# Schematic_Buttons_Luximetro.net
KiCad netlist of a schematic drawn in Altium Designer
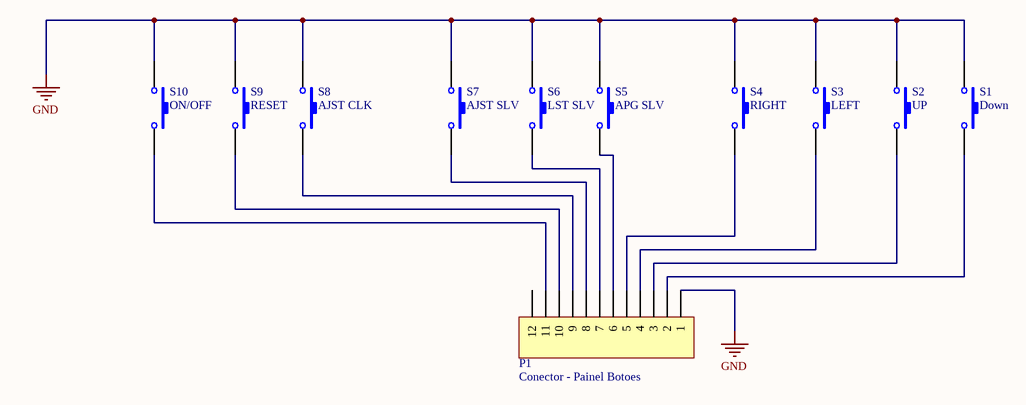
[diagram p0: Schematic_Buttons_Luximetro.SchDoc]

(export (version "E")
  (design (tool "Eeschema 10.0.6"))
  (components
    (comp (ref "P1")
      (value "Conector - Painel Botoes")
      (footprint "HDR1X12")
      (description "Header, 12-Pin")
      (fields (field (name "PUBLISHER") "Altium Limited"))
      (libsource (lib "Miscellaneous Connectors") (part "Header 12"))
    )
    (comp (ref "S1")
      (value "Down")
      (footprint "SPST-2")
      (description "Switch")
      (fields (field (name "PUBLISHER") "Altium Limited"))
      (libsource (lib "Miscellaneous Devices") (part "SW-PB"))
    )
    (comp (ref "S2")
      (value "UP")
      (footprint "SPST-2")
      (description "Switch")
      (fields (field (name "PUBLISHER") "Altium Limited"))
      (libsource (lib "Miscellaneous Devices") (part "SW-PB"))
    )
    (comp (ref "S3")
      (value "LEFT")
      (footprint "SPST-2")
      (description "Switch")
      (fields (field (name "PUBLISHER") "Altium Limited"))
      (libsource (lib "Miscellaneous Devices") (part "SW-PB"))
    )
    (comp (ref "S4")
      (value "RIGHT")
      (footprint "SPST-2")
      (description "Switch")
      (fields (field (name "PUBLISHER") "Altium Limited"))
      (libsource (lib "Miscellaneous Devices") (part "SW-PB"))
    )
    (comp (ref "S5")
      (value "APG SLV")
      (footprint "SPST-2")
      (description "Switch")
      (fields (field (name "PUBLISHER") "Altium Limited"))
      (libsource (lib "Miscellaneous Devices") (part "SW-PB"))
    )
    (comp (ref "S6")
      (value "LST SLV")
      (footprint "SPST-2")
      (description "Switch")
      (fields (field (name "PUBLISHER") "Altium Limited"))
      (libsource (lib "Miscellaneous Devices") (part "SW-PB"))
    )
    (comp (ref "S7")
      (value "AJST SLV")
      (footprint "SPST-2")
      (description "Switch")
      (fields (field (name "PUBLISHER") "Altium Limited"))
      (libsource (lib "Miscellaneous Devices") (part "SW-PB"))
    )
    (comp (ref "S8")
      (value "AJST CLK")
      (footprint "SPST-2")
      (description "Switch")
      (fields (field (name "PUBLISHER") "Altium Limited"))
      (libsource (lib "Miscellaneous Devices") (part "SW-PB"))
    )
    (comp (ref "S9")
      (value "RESET")
      (footprint "SPST-2")
      (description "Switch")
      (fields (field (name "PUBLISHER") "Altium Limited"))
      (libsource (lib "Miscellaneous Devices") (part "SW-PB"))
    )
    (comp (ref "S10")
      (value "ON/OFF")
      (footprint "SPST-2")
      (description "Switch")
      (fields (field (name "PUBLISHER") "Altium Limited"))
      (libsource (lib "Miscellaneous Devices") (part "SW-PB"))
    )
  )
  (nets
    (net (code "1") (name "GND") (class "Default")
      (node (ref "P1") (pin "1") (pinfunction "1_1") (pintype "passive"))
      (node (ref "S1") (pin "1") (pinfunction "1_1") (pintype "passive"))
      (node (ref "S10") (pin "1") (pinfunction "1_1") (pintype "passive"))
      (node (ref "S2") (pin "1") (pinfunction "1_1") (pintype "passive"))
      (node (ref "S3") (pin "1") (pinfunction "1_1") (pintype "passive"))
      (node (ref "S4") (pin "1") (pinfunction "1_1") (pintype "passive"))
      (node (ref "S5") (pin "1") (pinfunction "1_1") (pintype "passive"))
      (node (ref "S6") (pin "1") (pinfunction "1_1") (pintype "passive"))
      (node (ref "S7") (pin "1") (pinfunction "1_1") (pintype "passive"))
      (node (ref "S8") (pin "1") (pinfunction "1_1") (pintype "passive"))
      (node (ref "S9") (pin "1") (pinfunction "1_1") (pintype "passive"))
    )
    (net (code "2") (name "Net-(P1-Pad2)") (class "Default")
      (node (ref "P1") (pin "2") (pinfunction "2_2") (pintype "passive"))
      (node (ref "S1") (pin "2") (pinfunction "2_2") (pintype "passive"))
    )
    (net (code "3") (name "Net-(P1-Pad3)") (class "Default")
      (node (ref "P1") (pin "3") (pinfunction "3_3") (pintype "passive"))
      (node (ref "S2") (pin "2") (pinfunction "2_2") (pintype "passive"))
    )
    (net (code "4") (name "Net-(P1-Pad4)") (class "Default")
      (node (ref "P1") (pin "4") (pinfunction "4_4") (pintype "passive"))
      (node (ref "S3") (pin "2") (pinfunction "2_2") (pintype "passive"))
    )
    (net (code "5") (name "Net-(P1-Pad5)") (class "Default")
      (node (ref "P1") (pin "5") (pinfunction "5_5") (pintype "passive"))
      (node (ref "S4") (pin "2") (pinfunction "2_2") (pintype "passive"))
    )
    (net (code "6") (name "Net-(P1-Pad6)") (class "Default")
      (node (ref "P1") (pin "6") (pinfunction "6_6") (pintype "passive"))
      (node (ref "S5") (pin "2") (pinfunction "2_2") (pintype "passive"))
    )
    (net (code "7") (name "Net-(P1-Pad7)") (class "Default")
      (node (ref "P1") (pin "7") (pinfunction "7_7") (pintype "passive"))
      (node (ref "S6") (pin "2") (pinfunction "2_2") (pintype "passive"))
    )
    (net (code "8") (name "Net-(P1-Pad8)") (class "Default")
      (node (ref "P1") (pin "8") (pinfunction "8_8") (pintype "passive"))
      (node (ref "S7") (pin "2") (pinfunction "2_2") (pintype "passive"))
    )
    (net (code "9") (name "Net-(P1-Pad9)") (class "Default")
      (node (ref "P1") (pin "9") (pinfunction "9_9") (pintype "passive"))
      (node (ref "S8") (pin "2") (pinfunction "2_2") (pintype "passive"))
    )
    (net (code "10") (name "Net-(P1-Pad10)") (class "Default")
      (node (ref "P1") (pin "10") (pinfunction "10_10") (pintype "passive"))
      (node (ref "S9") (pin "2") (pinfunction "2_2") (pintype "passive"))
    )
    (net (code "11") (name "Net-(P1-Pad11)") (class "Default")
      (node (ref "P1") (pin "11") (pinfunction "11_11") (pintype "passive"))
      (node (ref "S10") (pin "2") (pinfunction "2_2") (pintype "passive"))
    )
    (net (code "12") (name "unconnected-(P1-Pad12)") (class "Default")
      (node (ref "P1") (pin "12") (pinfunction "12_12") (pintype "passive"))
    )
  )
)
